# Voltage_Source.net
KiCad netlist of a schematic drawn in Altium Designer
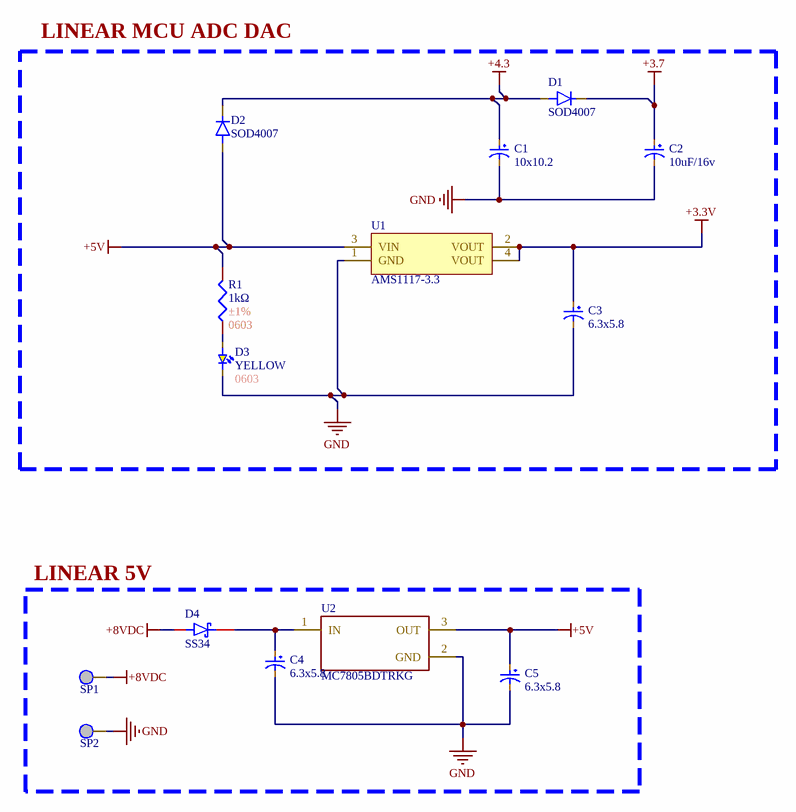
[diagram p0: Voltage Source.SchDoc]

(export (version "E")
  (design (tool "Eeschema 10.0.6"))
  (components
    (comp (ref "C1")
      (value "10x10.2")
      (footprint "C_10x10.2mm_Aluminum_SMD")
      (description "1000uF 16V ±20% 347mA@120Hz SMD,D10xL10.2mm Aluminum Electrolytic Capacitors RoHS")
      (fields (field (name "MANUFACTURER") "ROQANG") (field (name "MFR. PART #") "RVT1C102M1010"))
      (libsource (lib "Capital") (part "C_10x10.2_Aluminum_SMD"))
    )
    (comp (ref "C2")
      (value "10uF/16v")
      (footprint "C_4.3x5_Aluminum_smd")
      (description "10ÂµF 16V Aluminum Electrolytic Capacitors Radial, Can - SMD 2000 Hrs @ 105Â°C")
      (fields (field (name "MP") "EEE-HB1C100R") (field (name "MF") "Panasonic Electronic"))
      (libsource (lib "Capital") (part "C_4.3x5_Aluminum_SMD"))
    )
    (comp (ref "C3")
      (value "6.3x5.8")
      (footprint "C_6.3x5.8mm_Aluminum_SMD")
      (description "16V 10uF ±20% SMD,D6.3xL5.8mm Aluminum - Polymer Capacitors RoHS")
      (fields (field (name "MANUFACTURER") "Honor Elec") (field (name "MFR. PART #") "HV1C106M0605PZ"))
      (libsource (lib "Capital") (part "C_6.3x5.8_Aluminum_SMD"))
    )
    (comp (ref "C4")
      (value "6.3x5.8")
      (footprint "C_6.3x5.8mm_Aluminum_SMD")
      (description "16V 10uF ±20% SMD,D6.3xL5.8mm Aluminum - Polymer Capacitors RoHS")
      (fields (field (name "MANUFACTURER") "Honor Elec") (field (name "MFR. PART #") "HV1C106M0605PZ"))
      (libsource (lib "Capital") (part "C_6.3x5.8_Aluminum_SMD"))
    )
    (comp (ref "C5")
      (value "6.3x5.8")
      (footprint "C_6.3x5.8mm_Aluminum_SMD")
      (description "16V 10uF ±20% SMD,D6.3xL5.8mm Aluminum - Polymer Capacitors RoHS")
      (fields (field (name "MANUFACTURER") "Honor Elec") (field (name "MFR. PART #") "HV1C106M0605PZ"))
      (libsource (lib "Capital") (part "C_6.3x5.8_Aluminum_SMD"))
    )
    (comp (ref "D1")
      (value "SOD4007")
      (footprint "SOD4007")
      (description "1A Independent 1kV 1.1V@1A SOD-123FL Diodes - General Purpose ROHS")
      (fields
        (field (name "MANUFACTURER") "MDD(Microdiode Semiconductor)")
        (field (name "LCSC PART #") "C18124")
      )
      (libsource (lib "Diode") (part "SOD4007"))
    )
    (comp (ref "D2")
      (value "SOD4007")
      (footprint "SOD4007")
      (description "1A Independent 1kV 1.1V@1A SOD-123FL Diodes - General Purpose ROHS")
      (fields
        (field (name "MANUFACTURER") "MDD(Microdiode Semiconductor)")
        (field (name "LCSC PART #") "C18124")
      )
      (libsource (lib "Diode") (part "SOD4007"))
    )
    (comp (ref "D3")
      (value "YELLOW")
      (footprint "LED0603")
      (description "25mcd~40mcd Water Clear -40℃~+85℃ 624nm Red 120° 60mW 0402 LED Indication - Discrete ROHS")
      (fields
        (field (name "MANUFACTURER") "XINGLIGHT")
        (field (name "MFR. PART #") "XL-1005UGC")
        (field (name "PACKAGE") "0603")
      )
      (libsource (lib "LED") (part "D0603_YELLOW"))
    )
    (comp (ref "D4")
      (value "SS34")
      (footprint "SS34")
      (description "40V Independent 3A 550mV@3A SMA(DO-214AC) Schottky Diodes ROHS")
      (fields
        (field (name "MANUFACTURER") "MDD(Microdiode Semiconductor)")
        (field (name "LCSC PART #") "C8678")
      )
      (libsource (lib "Diode") (part "SS34"))
    )
    (comp (ref "R1")
      (value "1kΩ")
      (footprint "R0603")
      (description "62.5mW Thick Film Resistor 50V ±1% ±200ppm/℃ 10Ω 0402 Chip Resistor - Surface Mount ROHS")
      (fields
        (field (name "MANUFACTURER") "YAGEO")
        (field (name "MFR. PART #") "RC0402FR-0710RL")
        (field (name "TOLERANCE") "±1%")
        (field (name "PACKAGE") "0603")
      )
      (libsource (lib "Resistor") (part "R0603_1kΩ_±1%"))
    )
    (comp (ref "SP1") (value "SP") (footprint "SP") (libsource (lib "Other") (part "SP")))
    (comp (ref "SP2") (value "SP") (footprint "SP") (libsource (lib "Other") (part "SP")))
    (comp (ref "U1")
      (value "AMS1117-3.3")
      (footprint "AMS1117-3.3")
      (fields
        (field (name "MANUFACTURER") "Advanced Monolithic Systems")
        (field (name "LCSC PART #") "C6186")
      )
      (libsource (lib "IC") (part "AMS1117-3.3"))
    )
    (comp (ref "U2")
      (value "MC7805BDTRKG")
      (footprint "7805")
      (fields (field (name "MANUFACTURER") "onsemi") (field (name "LCSC PART #") "C110908"))
      (libsource (lib "IC") (part "7805"))
    )
  )
  (nets
    (net (code "1") (name "+3.3V") (class "Default")
      (node (ref "C3") (pin "1") (pinfunction "1_1") (pintype "passive"))
      (node (ref "U1") (pin "2") (pinfunction "VOUT_2") (pintype "passive"))
      (node (ref "U1") (pin "4") (pinfunction "VOUT_4") (pintype "passive"))
    )
    (net (code "2") (name "+3.7") (class "Default")
      (node (ref "C2") (pin "1") (pinfunction "1_1") (pintype "passive"))
      (node (ref "D1") (pin "1") (pinfunction "C_1") (pintype "passive"))
    )
    (net (code "3") (name "+4.3") (class "Default")
      (node (ref "C1") (pin "1") (pinfunction "1_1") (pintype "passive"))
      (node (ref "D1") (pin "2") (pinfunction "A_2") (pintype "passive"))
      (node (ref "D2") (pin "1") (pinfunction "C_1") (pintype "passive"))
    )
    (net (code "4") (name "+5V") (class "Default")
      (node (ref "C5") (pin "1") (pinfunction "1_1") (pintype "passive"))
      (node (ref "D2") (pin "2") (pinfunction "A_2") (pintype "passive"))
      (node (ref "R1") (pin "2") (pinfunction "2_2") (pintype "passive"))
      (node (ref "U1") (pin "3") (pinfunction "VIN_3") (pintype "passive"))
      (node (ref "U2") (pin "3") (pinfunction "OUT_3") (pintype "passive"))
    )
    (net (code "5") (name "+8VDC") (class "Default")
      (node (ref "D4") (pin "2") (pinfunction "2_2") (pintype "passive"))
      (node (ref "SP1") (pin "1") (pinfunction "1_1") (pintype "passive"))
    )
    (net (code "6") (name "GND") (class "Default")
      (node (ref "C1") (pin "2") (pinfunction "2_2") (pintype "passive"))
      (node (ref "C2") (pin "2") (pinfunction "2_2") (pintype "passive"))
      (node (ref "C3") (pin "2") (pinfunction "2_2") (pintype "passive"))
      (node (ref "C4") (pin "2") (pinfunction "2_2") (pintype "passive"))
      (node (ref "C5") (pin "2") (pinfunction "2_2") (pintype "passive"))
      (node (ref "D3") (pin "1") (pinfunction "1_1") (pintype "passive"))
      (node (ref "SP2") (pin "1") (pinfunction "1_1") (pintype "passive"))
      (node (ref "U1") (pin "1") (pinfunction "GND_1") (pintype "passive"))
      (node (ref "U2") (pin "2") (pinfunction "GND_2") (pintype "power_in"))
    )
    (net (code "7") (name "Net-(D3-Pad2)") (class "Default")
      (node (ref "D3") (pin "2") (pinfunction "2_2") (pintype "passive"))
      (node (ref "R1") (pin "1") (pinfunction "1_1") (pintype "passive"))
    )
    (net (code "8") (name "Net-(U2-IN)") (class "Default")
      (node (ref "C4") (pin "1") (pinfunction "1_1") (pintype "passive"))
      (node (ref "D4") (pin "1") (pinfunction "1_1") (pintype "passive"))
      (node (ref "U2") (pin "1") (pinfunction "IN_1") (pintype "passive"))
    )
  )
)
